# MagnetometerBreakoutSCH.net
KiCad netlist of a schematic drawn in Altium Designer
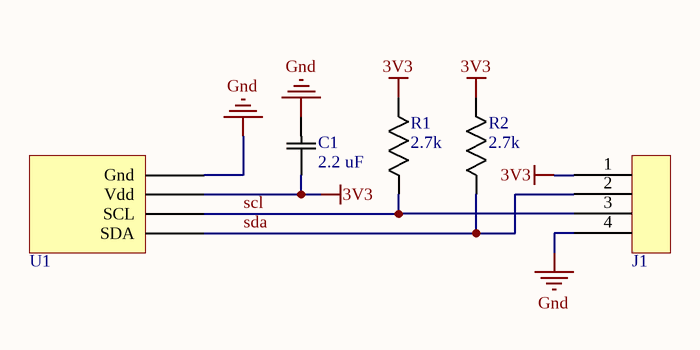
[diagram p0: MagnetometerBreakoutSCH.SchDoc]

(export (version "E")
  (design (tool "Eeschema 10.0.6"))
  (components
    (comp (ref "C1")
      (value "2.2 uF")
      (footprint "CAP 0603")
      (description "CAP CER 2.2UF 10V X5R 0603")
      (fields
        (field (name "MANUFACTURER_PART_NUMBER") "CL10A225KP8NNNC")
        (field (name "COPYRIGHT") "Copyright (C) 2022 Ultra Librarian. All rights reserved.")
      )
      (libsource (lib "MMCLib") (part "CL10A225KP8NNNC"))
    )
    (comp (ref "J1")
      (value "Header 0.1\" 4P")
      (footprint "0.1\" Header 4P")
      (description "CONN SIL HDR MALE PIN")
      (libsource (lib "MMCLib") (part "Header 0.1{dblquote} 4P"))
    )
    (comp (ref "R1")
      (value "2.7k")
      (footprint "RES 0805")
      (description "No Description Available")
      (fields
        (field (name "MANUFACTURER_PART_NUMBER") "RC0805JR-072K7L")
        (field (name "COPYRIGHT") "Copyright (C) 2022 Ultra Librarian. All rights reserved.")
      )
      (libsource (lib "MMCLib") (part "RC0805JR-072K7L"))
    )
    (comp (ref "R2")
      (value "2.7k")
      (footprint "RES 0805")
      (description "No Description Available")
      (fields
        (field (name "MANUFACTURER_PART_NUMBER") "RC0805JR-072K7L")
        (field (name "COPYRIGHT") "Copyright (C) 2022 Ultra Librarian. All rights reserved.")
      )
      (libsource (lib "MMCLib") (part "RC0805JR-072K7L"))
    )
    (comp (ref "U1")
      (value "MMC5603NJ")
      (footprint "4-WLP")
      (description "3-AXIS AMR MAGNETIC SENSOR")
      (libsource (lib "MMCLib") (part "MMC5603NJ"))
    )
  )
  (nets
    (net (code "1") (name "/scl") (class "Default")
      (node (ref "J1") (pin "3") (pintype "passive"))
      (node (ref "R1") (pin "1") (pinfunction "1_1") (pintype "passive"))
      (node (ref "U1") (pin "A2") (pinfunction "SCL_A2") (pintype "open_collector"))
    )
    (net (code "2") (name "/sda") (class "Default")
      (node (ref "J1") (pin "2") (pintype "passive"))
      (node (ref "R2") (pin "2") (pinfunction "2_2") (pintype "passive"))
      (node (ref "U1") (pin "B2") (pinfunction "SDA_B2") (pintype "open_collector"))
    )
    (net (code "3") (name "3V3") (class "Default")
      (node (ref "C1") (pin "2") (pinfunction "2_2") (pintype "passive"))
      (node (ref "J1") (pin "1") (pintype "passive"))
      (node (ref "R1") (pin "2") (pinfunction "2_2") (pintype "passive"))
      (node (ref "R2") (pin "1") (pinfunction "1_1") (pintype "passive"))
      (node (ref "U1") (pin "B1") (pinfunction "Vdd_B1") (pintype "power_in"))
    )
    (net (code "4") (name "Gnd") (class "Default")
      (node (ref "C1") (pin "1") (pinfunction "1_1") (pintype "passive"))
      (node (ref "J1") (pin "4") (pintype "passive"))
      (node (ref "U1") (pin "A1") (pinfunction "Gnd_A1") (pintype "power_in"))
    )
  )
)
